# SingleNixie.net
KiCad netlist of a schematic drawn in EAGLE
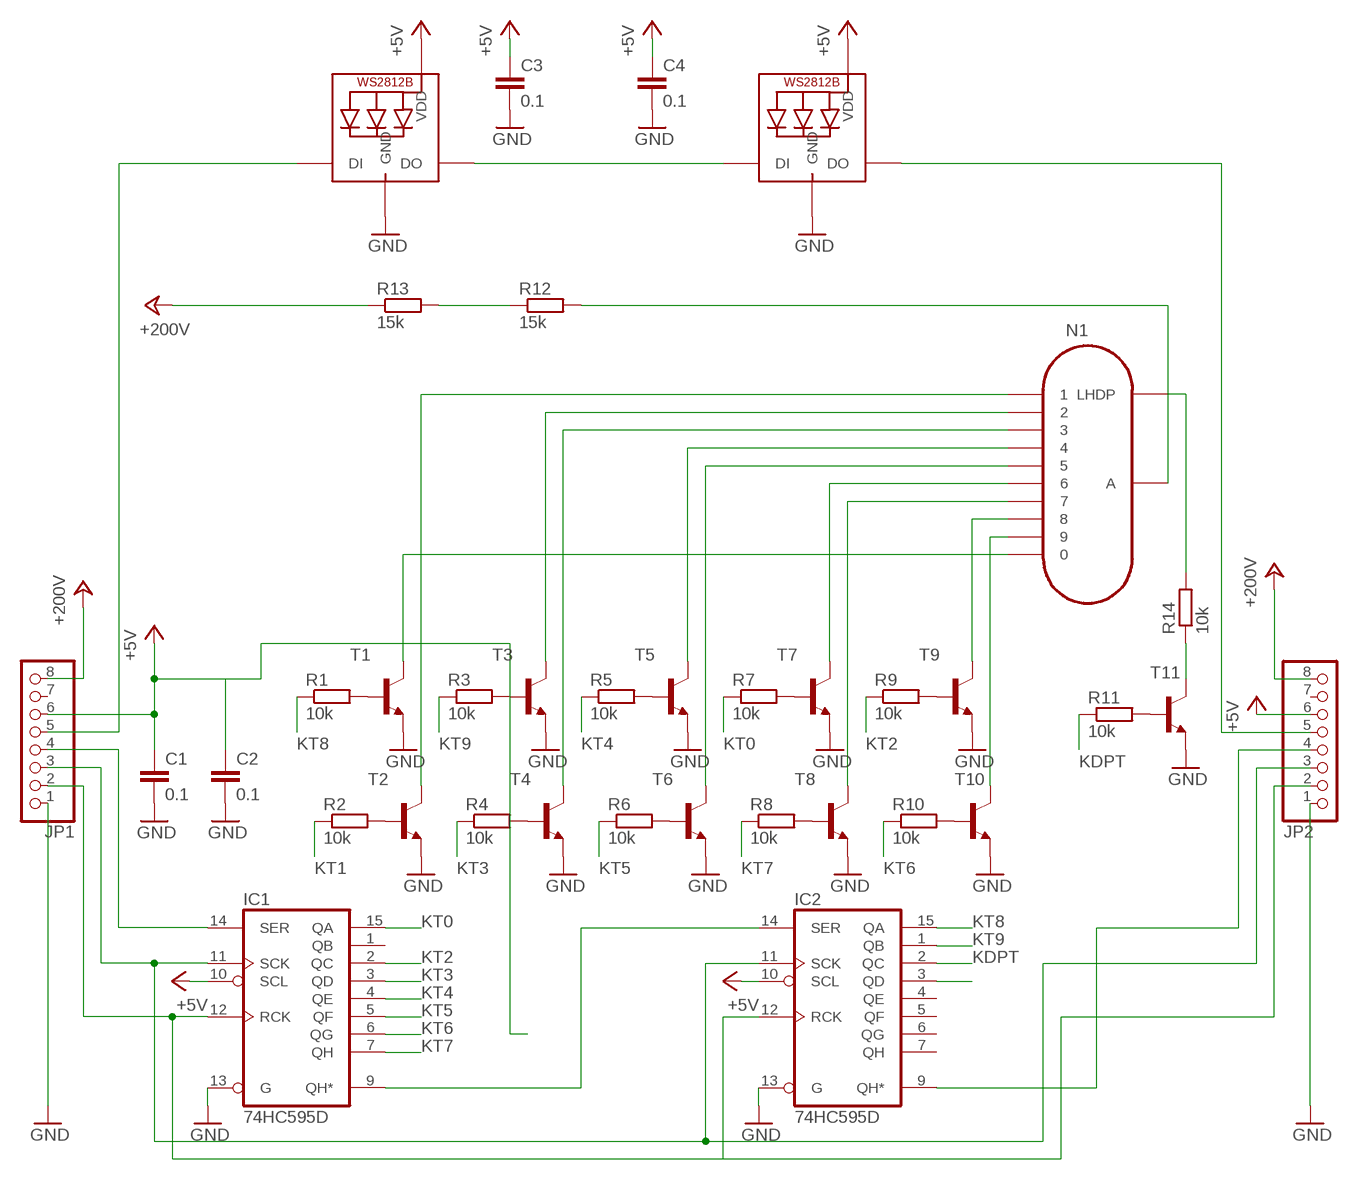
[diagram p0: schematic, sheet 1]

(export (version "E")
  (design (tool "Eeschema 10.0.6"))
  (components
    (comp (ref "C1")
      (value "0.1")
      (footprint "eagle-import:C0805")
      (libsource (lib "eagle-import") (part "C-EUC0805"))
    )
    (comp (ref "C2")
      (value "0.1")
      (footprint "eagle-import:C0805")
      (libsource (lib "eagle-import") (part "C-EUC0805"))
    )
    (comp (ref "C3")
      (value "0.1")
      (footprint "eagle-import:C0805")
      (libsource (lib "eagle-import") (part "C-EUC0805"))
    )
    (comp (ref "C4")
      (value "0.1")
      (footprint "eagle-import:C0805")
      (libsource (lib "eagle-import") (part "C-EUC0805"))
    )
    (comp (ref "IC1")
      (value "74HC595D")
      (footprint "eagle-import:SO16")
      (libsource (lib "eagle-import") (part "74595DHC"))
    )
    (comp (ref "IC2")
      (value "74HC595D")
      (footprint "eagle-import:SO16")
      (libsource (lib "eagle-import") (part "74595DHC"))
    )
    (comp (ref "JP1")
      (value "HEADER-1X8ROUND")
      (footprint "eagle-import:1X08_ROUND")
      (libsource (lib "eagle-import") (part "HEADER-1X8ROUND"))
    )
    (comp (ref "JP2")
      (value "HEADER-1X8ROUND")
      (footprint "eagle-import:1X08_ROUND")
      (libsource (lib "eagle-import") (part "HEADER-1X8ROUND"))
    )
    (comp (ref "LED1")
      (value "WS2812B3535")
      (footprint "eagle-import:LED3535")
      (libsource (lib "eagle-import") (part "WS2812B3535"))
    )
    (comp (ref "LED2")
      (value "WS2812B3535")
      (footprint "eagle-import:LED3535")
      (libsource (lib "eagle-import") (part "WS2812B3535"))
    )
    (comp (ref "N1")
      (value "IN-12B1.5MM")
      (footprint "eagle-import:IN-12-1.5")
      (libsource (lib "eagle-import") (part "IN-12B1.5MM"))
    )
    (comp (ref "R1")
      (value "10k")
      (footprint "eagle-import:R0805")
      (libsource (lib "eagle-import") (part "R-EU_R0805"))
    )
    (comp (ref "R2")
      (value "10k")
      (footprint "eagle-import:R0805")
      (libsource (lib "eagle-import") (part "R-EU_R0805"))
    )
    (comp (ref "R3")
      (value "10k")
      (footprint "eagle-import:R0805")
      (libsource (lib "eagle-import") (part "R-EU_R0805"))
    )
    (comp (ref "R4")
      (value "10k")
      (footprint "eagle-import:R0805")
      (libsource (lib "eagle-import") (part "R-EU_R0805"))
    )
    (comp (ref "R5")
      (value "10k")
      (footprint "eagle-import:R0805")
      (libsource (lib "eagle-import") (part "R-EU_R0805"))
    )
    (comp (ref "R6")
      (value "10k")
      (footprint "eagle-import:R0805")
      (libsource (lib "eagle-import") (part "R-EU_R0805"))
    )
    (comp (ref "R7")
      (value "10k")
      (footprint "eagle-import:R0805")
      (libsource (lib "eagle-import") (part "R-EU_R0805"))
    )
    (comp (ref "R8")
      (value "10k")
      (footprint "eagle-import:R0805")
      (libsource (lib "eagle-import") (part "R-EU_R0805"))
    )
    (comp (ref "R9")
      (value "10k")
      (footprint "eagle-import:R0805")
      (libsource (lib "eagle-import") (part "R-EU_R0805"))
    )
    (comp (ref "R10")
      (value "10k")
      (footprint "eagle-import:R0805")
      (libsource (lib "eagle-import") (part "R-EU_R0805"))
    )
    (comp (ref "R11")
      (value "10k")
      (footprint "eagle-import:R0805")
      (libsource (lib "eagle-import") (part "R-EU_R0805"))
    )
    (comp (ref "R12")
      (value "15k")
      (footprint "eagle-import:R0805")
      (libsource (lib "eagle-import") (part "R-EU_R0805"))
    )
    (comp (ref "R13")
      (value "15k")
      (footprint "eagle-import:R0805")
      (libsource (lib "eagle-import") (part "R-EU_R0805"))
    )
    (comp (ref "R14")
      (value "10k")
      (footprint "eagle-import:R0805")
      (libsource (lib "eagle-import") (part "R-EU_R0805"))
    )
    (comp (ref "T1")
      (value "MMBTA42LT1-NPN-SOT23-BEC")
      (footprint "eagle-import:SOT23-BEC")
      (libsource (lib "eagle-import") (part "-NPN-SOT23-BECMMBTA42LT1"))
    )
    (comp (ref "T2")
      (value "MMBTA42LT1-NPN-SOT23-BEC")
      (footprint "eagle-import:SOT23-BEC")
      (libsource (lib "eagle-import") (part "-NPN-SOT23-BECMMBTA42LT1"))
    )
    (comp (ref "T3")
      (value "MMBTA42LT1-NPN-SOT23-BEC")
      (footprint "eagle-import:SOT23-BEC")
      (libsource (lib "eagle-import") (part "-NPN-SOT23-BECMMBTA42LT1"))
    )
    (comp (ref "T4")
      (value "MMBTA42LT1-NPN-SOT23-BEC")
      (footprint "eagle-import:SOT23-BEC")
      (libsource (lib "eagle-import") (part "-NPN-SOT23-BECMMBTA42LT1"))
    )
    (comp (ref "T5")
      (value "MMBTA42LT1-NPN-SOT23-BEC")
      (footprint "eagle-import:SOT23-BEC")
      (libsource (lib "eagle-import") (part "-NPN-SOT23-BECMMBTA42LT1"))
    )
    (comp (ref "T6")
      (value "MMBTA42LT1-NPN-SOT23-BEC")
      (footprint "eagle-import:SOT23-BEC")
      (libsource (lib "eagle-import") (part "-NPN-SOT23-BECMMBTA42LT1"))
    )
    (comp (ref "T7")
      (value "MMBTA42LT1-NPN-SOT23-BEC")
      (footprint "eagle-import:SOT23-BEC")
      (libsource (lib "eagle-import") (part "-NPN-SOT23-BECMMBTA42LT1"))
    )
    (comp (ref "T8")
      (value "MMBTA42LT1-NPN-SOT23-BEC")
      (footprint "eagle-import:SOT23-BEC")
      (libsource (lib "eagle-import") (part "-NPN-SOT23-BECMMBTA42LT1"))
    )
    (comp (ref "T9")
      (value "MMBTA42LT1-NPN-SOT23-BEC")
      (footprint "eagle-import:SOT23-BEC")
      (libsource (lib "eagle-import") (part "-NPN-SOT23-BECMMBTA42LT1"))
    )
    (comp (ref "T10")
      (value "MMBTA42LT1-NPN-SOT23-BEC")
      (footprint "eagle-import:SOT23-BEC")
      (libsource (lib "eagle-import") (part "-NPN-SOT23-BECMMBTA42LT1"))
    )
    (comp (ref "T11")
      (value "MMBTA42LT1-NPN-SOT23-BEC")
      (footprint "eagle-import:SOT23-BEC")
      (libsource (lib "eagle-import") (part "-NPN-SOT23-BECMMBTA42LT1"))
    )
  )
  (nets
    (net (code "1") (name "+5V") (class "Default")
      (node (ref "C1") (pin "1") (pinfunction "1_1") (pintype "passive"))
      (node (ref "C2") (pin "1") (pinfunction "1_1") (pintype "passive"))
      (node (ref "C3") (pin "1") (pinfunction "1_1") (pintype "passive"))
      (node (ref "C4") (pin "1") (pinfunction "1_1") (pintype "passive"))
      (node (ref "IC1") (pin "10") (pinfunction "SCL_10") (pintype "input"))
      (node (ref "IC2") (pin "10") (pinfunction "SCL_10") (pintype "input"))
      (node (ref "JP1") (pin "6") (pinfunction "6_6") (pintype "passive"))
      (node (ref "JP2") (pin "6") (pinfunction "6_6") (pintype "passive"))
      (node (ref "LED1") (pin "2") (pinfunction "VDD_2") (pintype "power_in"))
      (node (ref "LED2") (pin "2") (pinfunction "VDD_2") (pintype "power_in"))
    )
    (net (code "2") (name "+200V") (class "Default")
      (node (ref "JP1") (pin "8") (pinfunction "8_8") (pintype "passive"))
      (node (ref "JP2") (pin "8") (pinfunction "8_8") (pintype "passive"))
      (node (ref "R13") (pin "1") (pinfunction "1_1") (pintype "passive"))
    )
    (net (code "3") (name "/KDPT") (class "Default")
      (node (ref "IC2") (pin "2") (pinfunction "QC_2") (pintype "tri_state"))
      (node (ref "R11") (pin "1") (pinfunction "1_1") (pintype "passive"))
    )
    (net (code "4") (name "/KT0") (class "Default")
      (node (ref "IC1") (pin "15") (pinfunction "QA_15") (pintype "tri_state"))
      (node (ref "R7") (pin "1") (pinfunction "1_1") (pintype "passive"))
    )
    (net (code "5") (name "/KT1") (class "Default")
      (node (ref "IC2") (pin "3") (pinfunction "QD_3") (pintype "tri_state"))
      (node (ref "R2") (pin "1") (pinfunction "1_1") (pintype "passive"))
    )
    (net (code "6") (name "/KT2") (class "Default")
      (node (ref "IC1") (pin "2") (pinfunction "QC_2") (pintype "tri_state"))
      (node (ref "R9") (pin "1") (pinfunction "1_1") (pintype "passive"))
    )
    (net (code "7") (name "/KT3") (class "Default")
      (node (ref "IC1") (pin "3") (pinfunction "QD_3") (pintype "tri_state"))
      (node (ref "R4") (pin "1") (pinfunction "1_1") (pintype "passive"))
    )
    (net (code "8") (name "/KT4") (class "Default")
      (node (ref "IC1") (pin "4") (pinfunction "QE_4") (pintype "tri_state"))
      (node (ref "R5") (pin "1") (pinfunction "1_1") (pintype "passive"))
    )
    (net (code "9") (name "/KT5") (class "Default")
      (node (ref "IC1") (pin "5") (pinfunction "QF_5") (pintype "tri_state"))
      (node (ref "R6") (pin "1") (pinfunction "1_1") (pintype "passive"))
    )
    (net (code "10") (name "/KT6") (class "Default")
      (node (ref "IC1") (pin "6") (pinfunction "QG_6") (pintype "tri_state"))
      (node (ref "R10") (pin "1") (pinfunction "1_1") (pintype "passive"))
    )
    (net (code "11") (name "/KT7") (class "Default")
      (node (ref "IC1") (pin "7") (pinfunction "QH_7") (pintype "tri_state"))
      (node (ref "R8") (pin "1") (pinfunction "1_1") (pintype "passive"))
    )
    (net (code "12") (name "/KT8") (class "Default")
      (node (ref "IC2") (pin "15") (pinfunction "QA_15") (pintype "tri_state"))
      (node (ref "R1") (pin "1") (pinfunction "1_1") (pintype "passive"))
    )
    (net (code "13") (name "/KT9") (class "Default")
      (node (ref "IC2") (pin "1") (pinfunction "QB_1") (pintype "tri_state"))
      (node (ref "R3") (pin "1") (pinfunction "1_1") (pintype "passive"))
    )
    (net (code "14") (name "GND") (class "Default")
      (node (ref "C1") (pin "2") (pinfunction "2_2") (pintype "passive"))
      (node (ref "C2") (pin "2") (pinfunction "2_2") (pintype "passive"))
      (node (ref "C3") (pin "2") (pinfunction "2_2") (pintype "passive"))
      (node (ref "C4") (pin "2") (pinfunction "2_2") (pintype "passive"))
      (node (ref "IC1") (pin "13") (pinfunction "G_13") (pintype "input"))
      (node (ref "IC2") (pin "13") (pinfunction "G_13") (pintype "input"))
      (node (ref "JP1") (pin "1") (pinfunction "1_1") (pintype "passive"))
      (node (ref "JP2") (pin "1") (pinfunction "1_1") (pintype "passive"))
      (node (ref "LED1") (pin "4") (pinfunction "GND_4") (pintype "power_in"))
      (node (ref "LED2") (pin "4") (pinfunction "GND_4") (pintype "power_in"))
      (node (ref "T1") (pin "E") (pinfunction "E_E") (pintype "passive"))
      (node (ref "T10") (pin "E") (pinfunction "E_E") (pintype "passive"))
      (node (ref "T11") (pin "E") (pinfunction "E_E") (pintype "passive"))
      (node (ref "T2") (pin "E") (pinfunction "E_E") (pintype "passive"))
      (node (ref "T3") (pin "E") (pinfunction "E_E") (pintype "passive"))
      (node (ref "T4") (pin "E") (pinfunction "E_E") (pintype "passive"))
      (node (ref "T5") (pin "E") (pinfunction "E_E") (pintype "passive"))
      (node (ref "T6") (pin "E") (pinfunction "E_E") (pintype "passive"))
      (node (ref "T7") (pin "E") (pinfunction "E_E") (pintype "passive"))
      (node (ref "T8") (pin "E") (pinfunction "E_E") (pintype "passive"))
      (node (ref "T9") (pin "E") (pinfunction "E_E") (pintype "passive"))
    )
    (net (code "15") (name "Net-(IC1A-QH*)") (class "Default")
      (node (ref "IC1") (pin "9") (pinfunction "QH*_9") (pintype "tri_state"))
      (node (ref "IC2") (pin "14") (pinfunction "SER_14") (pintype "input"))
    )
    (net (code "16") (name "Net-(IC1A-RCK)") (class "Default")
      (node (ref "IC1") (pin "12") (pinfunction "RCK_12") (pintype "input"))
      (node (ref "IC2") (pin "12") (pinfunction "RCK_12") (pintype "input"))
      (node (ref "JP1") (pin "2") (pinfunction "2_2") (pintype "passive"))
      (node (ref "JP2") (pin "2") (pinfunction "2_2") (pintype "passive"))
    )
    (net (code "17") (name "Net-(IC1A-SCK)") (class "Default")
      (node (ref "IC1") (pin "11") (pinfunction "SCK_11") (pintype "input"))
      (node (ref "IC2") (pin "11") (pinfunction "SCK_11") (pintype "input"))
      (node (ref "JP1") (pin "3") (pinfunction "3_3") (pintype "passive"))
      (node (ref "JP2") (pin "3") (pinfunction "3_3") (pintype "passive"))
    )
    (net (code "18") (name "Net-(IC1A-SER)") (class "Default")
      (node (ref "IC1") (pin "14") (pinfunction "SER_14") (pintype "input"))
      (node (ref "JP1") (pin "4") (pinfunction "4_4") (pintype "passive"))
    )
    (net (code "19") (name "Net-(IC2A-QH*)") (class "Default")
      (node (ref "IC2") (pin "9") (pinfunction "QH*_9") (pintype "tri_state"))
      (node (ref "JP2") (pin "4") (pinfunction "4_4") (pintype "passive"))
    )
    (net (code "20") (name "Net-(LED1-DI)") (class "Default")
      (node (ref "JP1") (pin "5") (pinfunction "5_5") (pintype "passive"))
      (node (ref "LED1") (pin "1") (pinfunction "DI_1") (pintype "input"))
    )
    (net (code "21") (name "Net-(LED1-DO)") (class "Default")
      (node (ref "LED1") (pin "3") (pinfunction "DO_3") (pintype "output"))
      (node (ref "LED2") (pin "1") (pinfunction "DI_1") (pintype "input"))
    )
    (net (code "22") (name "Net-(LED2-DO)") (class "Default")
      (node (ref "JP2") (pin "5") (pinfunction "5_5") (pintype "passive"))
      (node (ref "LED2") (pin "3") (pinfunction "DO_3") (pintype "output"))
    )
    (net (code "23") (name "Net-(N1-Pad0)") (class "Default")
      (node (ref "N1") (pin "0") (pinfunction "0_0") (pintype "bidirectional"))
      (node (ref "T1") (pin "C") (pinfunction "C_C") (pintype "passive"))
    )
    (net (code "24") (name "Net-(N1-Pad1)") (class "Default")
      (node (ref "N1") (pin "1") (pinfunction "1_1") (pintype "bidirectional"))
      (node (ref "T2") (pin "C") (pinfunction "C_C") (pintype "passive"))
    )
    (net (code "25") (name "Net-(N1-Pad2)") (class "Default")
      (node (ref "N1") (pin "2") (pinfunction "2_2") (pintype "bidirectional"))
      (node (ref "T3") (pin "C") (pinfunction "C_C") (pintype "passive"))
    )
    (net (code "26") (name "Net-(N1-Pad3)") (class "Default")
      (node (ref "N1") (pin "3") (pinfunction "3_3") (pintype "bidirectional"))
      (node (ref "T4") (pin "C") (pinfunction "C_C") (pintype "passive"))
    )
    (net (code "27") (name "Net-(N1-Pad4)") (class "Default")
      (node (ref "N1") (pin "4") (pinfunction "4_4") (pintype "bidirectional"))
      (node (ref "T5") (pin "C") (pinfunction "C_C") (pintype "passive"))
    )
    (net (code "28") (name "Net-(N1-Pad5)") (class "Default")
      (node (ref "N1") (pin "5") (pinfunction "5_5") (pintype "bidirectional"))
      (node (ref "T6") (pin "C") (pinfunction "C_C") (pintype "passive"))
    )
    (net (code "29") (name "Net-(N1-Pad6)") (class "Default")
      (node (ref "N1") (pin "6") (pinfunction "6_6") (pintype "bidirectional"))
      (node (ref "T7") (pin "C") (pinfunction "C_C") (pintype "passive"))
    )
    (net (code "30") (name "Net-(N1-Pad7)") (class "Default")
      (node (ref "N1") (pin "7") (pinfunction "7_7") (pintype "bidirectional"))
      (node (ref "T8") (pin "C") (pinfunction "C_C") (pintype "passive"))
    )
    (net (code "31") (name "Net-(N1-Pad8)") (class "Default")
      (node (ref "N1") (pin "8") (pinfunction "8_8") (pintype "bidirectional"))
      (node (ref "T9") (pin "C") (pinfunction "C_C") (pintype "passive"))
    )
    (net (code "32") (name "Net-(N1-Pad9)") (class "Default")
      (node (ref "N1") (pin "9") (pinfunction "9_9") (pintype "bidirectional"))
      (node (ref "T10") (pin "C") (pinfunction "C_C") (pintype "passive"))
    )
    (net (code "33") (name "Net-(N1-PadA)") (class "Default")
      (node (ref "N1") (pin "A") (pinfunction "A_A") (pintype "bidirectional"))
      (node (ref "R12") (pin "2") (pinfunction "2_2") (pintype "passive"))
    )
    (net (code "34") (name "Net-(N1-PadLHDP)") (class "Default")
      (node (ref "N1") (pin "LHDP") (pinfunction "LHDP_LHDP") (pintype "bidirectional"))
      (node (ref "R14") (pin "2") (pinfunction "2_2") (pintype "passive"))
    )
    (net (code "35") (name "Net-(R1-Pad2)") (class "Default")
      (node (ref "R1") (pin "2") (pinfunction "2_2") (pintype "passive"))
      (node (ref "T1") (pin "B") (pinfunction "B_B") (pintype "passive"))
    )
    (net (code "36") (name "Net-(R2-Pad2)") (class "Default")
      (node (ref "R2") (pin "2") (pinfunction "2_2") (pintype "passive"))
      (node (ref "T2") (pin "B") (pinfunction "B_B") (pintype "passive"))
    )
    (net (code "37") (name "Net-(R3-Pad2)") (class "Default")
      (node (ref "R3") (pin "2") (pinfunction "2_2") (pintype "passive"))
      (node (ref "T3") (pin "B") (pinfunction "B_B") (pintype "passive"))
    )
    (net (code "38") (name "Net-(R4-Pad2)") (class "Default")
      (node (ref "R4") (pin "2") (pinfunction "2_2") (pintype "passive"))
      (node (ref "T4") (pin "B") (pinfunction "B_B") (pintype "passive"))
    )
    (net (code "39") (name "Net-(R5-Pad2)") (class "Default")
      (node (ref "R5") (pin "2") (pinfunction "2_2") (pintype "passive"))
      (node (ref "T5") (pin "B") (pinfunction "B_B") (pintype "passive"))
    )
    (net (code "40") (name "Net-(R6-Pad2)") (class "Default")
      (node (ref "R6") (pin "2") (pinfunction "2_2") (pintype "passive"))
      (node (ref "T6") (pin "B") (pinfunction "B_B") (pintype "passive"))
    )
    (net (code "41") (name "Net-(R7-Pad2)") (class "Default")
      (node (ref "R7") (pin "2") (pinfunction "2_2") (pintype "passive"))
      (node (ref "T7") (pin "B") (pinfunction "B_B") (pintype "passive"))
    )
    (net (code "42") (name "Net-(R8-Pad2)") (class "Default")
      (node (ref "R8") (pin "2") (pinfunction "2_2") (pintype "passive"))
      (node (ref "T8") (pin "B") (pinfunction "B_B") (pintype "passive"))
    )
    (net (code "43") (name "Net-(R9-Pad2)") (class "Default")
      (node (ref "R9") (pin "2") (pinfunction "2_2") (pintype "passive"))
      (node (ref "T9") (pin "B") (pinfunction "B_B") (pintype "passive"))
    )
    (net (code "44") (name "Net-(R10-Pad2)") (class "Default")
      (node (ref "R10") (pin "2") (pinfunction "2_2") (pintype "passive"))
      (node (ref "T10") (pin "B") (pinfunction "B_B") (pintype "passive"))
    )
    (net (code "45") (name "Net-(R11-Pad2)") (class "Default")
      (node (ref "R11") (pin "2") (pinfunction "2_2") (pintype "passive"))
      (node (ref "T11") (pin "B") (pinfunction "B_B") (pintype "passive"))
    )
    (net (code "46") (name "Net-(R12-Pad1)") (class "Default")
      (node (ref "R12") (pin "1") (pinfunction "1_1") (pintype "passive"))
      (node (ref "R13") (pin "2") (pinfunction "2_2") (pintype "passive"))
    )
    (net (code "47") (name "Net-(R14-Pad1)") (class "Default")
      (node (ref "R14") (pin "1") (pinfunction "1_1") (pintype "passive"))
      (node (ref "T11") (pin "C") (pinfunction "C_C") (pintype "passive"))
    )
    (net (code "48") (name "unconnected-(IC1A-QB-Pad1)") (class "Default")
      (node (ref "IC1") (pin "1") (pinfunction "QB_1") (pintype "tri_state"))
    )
    (net (code "49") (name "unconnected-(IC2A-QE-Pad4)") (class "Default")
      (node (ref "IC2") (pin "4") (pinfunction "QE_4") (pintype "tri_state"))
    )
    (net (code "50") (name "unconnected-(IC2A-QF-Pad5)") (class "Default")
      (node (ref "IC2") (pin "5") (pinfunction "QF_5") (pintype "tri_state"))
    )
    (net (code "51") (name "unconnected-(IC2A-QG-Pad6)") (class "Default")
      (node (ref "IC2") (pin "6") (pinfunction "QG_6") (pintype "tri_state"))
    )
    (net (code "52") (name "unconnected-(IC2A-QH-Pad7)") (class "Default")
      (node (ref "IC2") (pin "7") (pinfunction "QH_7") (pintype "tri_state"))
    )
    (net (code "53") (name "unconnected-(JP1-Pad7)") (class "Default")
      (node (ref "JP1") (pin "7") (pinfunction "7_7") (pintype "passive"))
    )
    (net (code "54") (name "unconnected-(JP2-Pad7)") (class "Default")
      (node (ref "JP2") (pin "7") (pinfunction "7_7") (pintype "passive"))
    )
  )
)
